# 1_Sch.net
KiCad netlist of a schematic drawn in Altium Designer
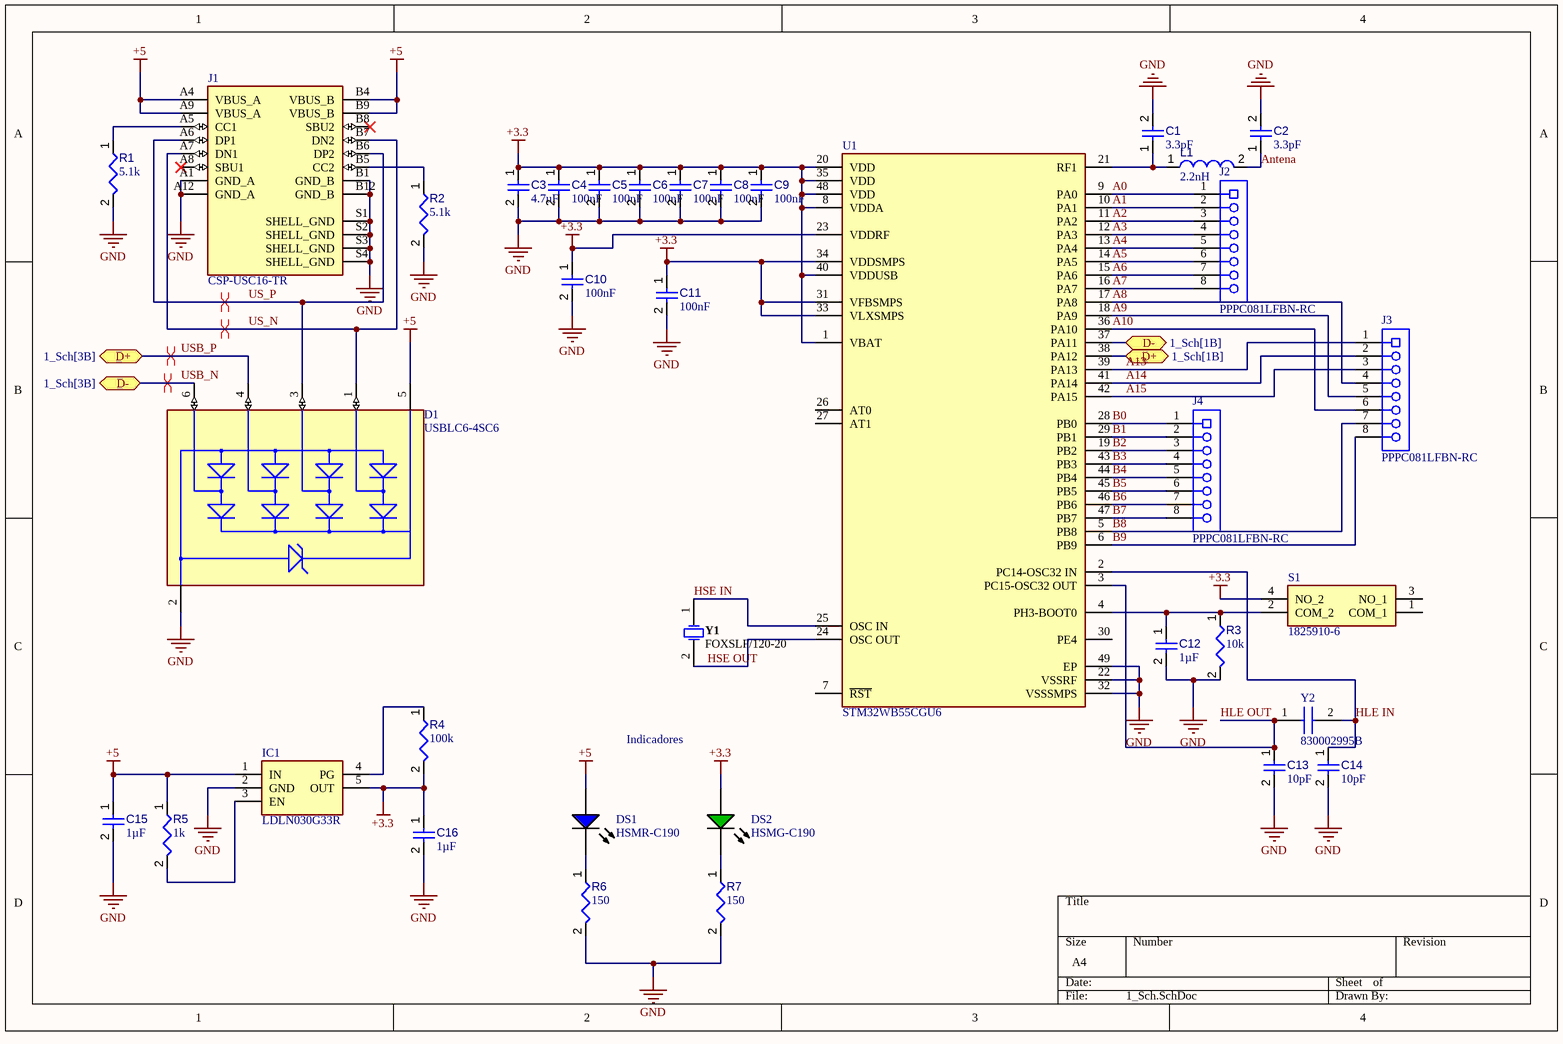
[diagram p0: 1_Sch.SchDoc]

(export (version "E")
  (design (tool "Eeschema 10.0.6"))
  (components
    (comp (ref "C1")
      (value "3.3pF")
      (footprint "CAPC1608X90X40NL10T20")
      (description "Chip Capacitor, 100 nF, +/- 10%, 50 V, 0603 (1608 Metric)")
      (fields (field (name "TOLERANCE") "10%") (field (name "Comment") "Capacitor 100 nF +/-10% 50 V 0603"))
      (libsource (lib "Universidad de Guadalajara") (part "CAP-NP-2"))
    )
    (comp (ref "C2")
      (value "3.3pF")
      (footprint "CAPC1608X90X40NL10T20")
      (description "Chip Capacitor, 100 nF, +/- 10%, 50 V, 0603 (1608 Metric)")
      (fields (field (name "TOLERANCE") "10%") (field (name "Comment") "Capacitor 100 nF +/-10% 50 V 0603"))
      (libsource (lib "Universidad de Guadalajara") (part "CAP-NP-2"))
    )
    (comp (ref "C3")
      (value "4.7uF")
      (footprint "CAPC1608X90X40NL10T20")
      (description "Chip Capacitor, 100 nF, +/- 10%, 50 V, 0603 (1608 Metric)")
      (fields (field (name "TOLERANCE") "10%") (field (name "Comment") "Capacitor 100 nF +/-10% 50 V 0603"))
      (libsource (lib "Universidad de Guadalajara") (part "CAP-NP-2"))
    )
    (comp (ref "C4")
      (value "100nF")
      (footprint "CAPC1608X90X40NL10T20")
      (description "Chip Capacitor, 100 nF, +/- 10%, 50 V, 0603 (1608 Metric)")
      (fields (field (name "TOLERANCE") "10%") (field (name "Comment") "Capacitor 100 nF +/-10% 50 V 0603"))
      (libsource (lib "Universidad de Guadalajara") (part "CAP-NP-2"))
    )
    (comp (ref "C5")
      (value "100nF")
      (footprint "CAPC1608X90X40NL10T20")
      (description "Chip Capacitor, 100 nF, +/- 10%, 50 V, 0603 (1608 Metric)")
      (fields (field (name "TOLERANCE") "10%") (field (name "Comment") "Capacitor 100 nF +/-10% 50 V 0603"))
      (libsource (lib "Universidad de Guadalajara") (part "CAP-NP-2"))
    )
    (comp (ref "C6")
      (value "100nF")
      (footprint "CAPC1608X90X40NL10T20")
      (description "Chip Capacitor, 100 nF, +/- 10%, 50 V, 0603 (1608 Metric)")
      (fields (field (name "TOLERANCE") "10%") (field (name "Comment") "Capacitor 100 nF +/-10% 50 V 0603"))
      (libsource (lib "Universidad de Guadalajara") (part "CAP-NP-2"))
    )
    (comp (ref "C7")
      (value "100nF")
      (footprint "CAPC1608X90X40NL10T20")
      (description "Chip Capacitor, 100 nF, +/- 10%, 50 V, 0603 (1608 Metric)")
      (fields (field (name "TOLERANCE") "10%") (field (name "Comment") "Capacitor 100 nF +/-10% 50 V 0603"))
      (libsource (lib "Universidad de Guadalajara") (part "CAP-NP-2"))
    )
    (comp (ref "C8")
      (value "100nF")
      (footprint "CAPC1608X90X40NL10T20")
      (description "Chip Capacitor, 100 nF, +/- 10%, 50 V, 0603 (1608 Metric)")
      (fields (field (name "TOLERANCE") "10%") (field (name "Comment") "Capacitor 100 nF +/-10% 50 V 0603"))
      (libsource (lib "Universidad de Guadalajara") (part "CAP-NP-2"))
    )
    (comp (ref "C9")
      (value "100nF")
      (footprint "CAPC1608X90X40NL10T20")
      (description "Chip Capacitor, 100 nF, +/- 10%, 50 V, 0603 (1608 Metric)")
      (fields (field (name "TOLERANCE") "10%") (field (name "Comment") "Capacitor 100 nF +/-10% 50 V 0603"))
      (libsource (lib "Universidad de Guadalajara") (part "CAP-NP-2"))
    )
    (comp (ref "C10")
      (value "100nF")
      (footprint "CAPC1608X90X40NL10T20")
      (description "Chip Capacitor, 100 nF, +/- 10%, 50 V, 0603 (1608 Metric)")
      (fields (field (name "TOLERANCE") "10%") (field (name "Comment") "Capacitor 100 nF +/-10% 50 V 0603"))
      (libsource (lib "Universidad de Guadalajara") (part "CAP-NP-2"))
    )
    (comp (ref "C11")
      (value "100nF")
      (footprint "CAPC1608X90X40NL10T20")
      (description "Chip Capacitor, 100 nF, +/- 10%, 50 V, 0603 (1608 Metric)")
      (fields (field (name "TOLERANCE") "10%") (field (name "Comment") "Capacitor 100 nF +/-10% 50 V 0603"))
      (libsource (lib "Universidad de Guadalajara") (part "CAP-NP-2"))
    )
    (comp (ref "C12")
      (value "1µF")
      (footprint "CAPC1608X94X35NL15T15")
      (description "Chip Capacitor, 1 uF, +/- 10%, 16 V, 0603 (1608 Metric)")
      (fields (field (name "TOLERANCE") "10%") (field (name "Comment") "Capacitor 1 uF +/- 10% 16 V 0603"))
      (libsource (lib "Universidad de Guadalajara") (part "CAP-NP-2"))
    )
    (comp (ref "C13")
      (value "10pF")
      (footprint "CAPC1608X90X40ML10T20")
      (description "Chip Capacitor, 10 pF, +/- 5%, 50 V, 0603 (1608 Metric)")
      (fields (field (name "TOLERANCE") "5%") (field (name "Comment") "Capacitor 10 pF +/- 5% 50 V 0603"))
      (libsource (lib "Universidad de Guadalajara") (part "CAP-NP-2"))
    )
    (comp (ref "C14")
      (value "10pF")
      (footprint "CAPC1608X90X40ML10T20")
      (description "Chip Capacitor, 10 pF, +/- 5%, 50 V, 0603 (1608 Metric)")
      (fields (field (name "TOLERANCE") "5%") (field (name "Comment") "Capacitor 10 pF +/- 5% 50 V 0603"))
      (libsource (lib "Universidad de Guadalajara") (part "CAP-NP-2"))
    )
    (comp (ref "C15")
      (value "1µF")
      (footprint "CAPC1608X90X35ML15T15")
      (description "Chip Capacitor, 1 uF, +/- 10%, 16 V, 0603 (1608 Metric)")
      (fields (field (name "TOLERANCE") "10%") (field (name "Comment") "Capacitor 1uF +/- 10% 16V 0603"))
      (libsource (lib "Universidad de Guadalajara") (part "CAP-NP-2"))
    )
    (comp (ref "C16")
      (value "1µF")
      (footprint "CAPC1608X90X35ML15T15")
      (description "Chip Capacitor, 1 uF, +/- 10%, 16 V, 0603 (1608 Metric)")
      (fields (field (name "TOLERANCE") "10%") (field (name "Comment") "Capacitor 1uF +/- 10% 16V 0603"))
      (libsource (lib "Universidad de Guadalajara") (part "CAP-NP-2"))
    )
    (comp (ref "D1")
      (value "USBLC6-4SC6")
      (footprint "FP-SOT23-6L-MFG")
      (description "TVS DIODE 5.25V 17V SOT23-6")
      (fields
        (field (name "MANUFACTURER") "STMicroelectronics")
        (field (name "OCTOPART") "https://octopart.com/usblc6-4sc6-stmicroelectronics-347147")
      )
      (libsource (lib "Altium Content Vault") (part "3e70b616ccdc4c88b528e1820c4a7da"))
    )
    (comp (ref "DS1")
      (value "HSMR-C190")
      (footprint "AVAG-HSMX-C190_V")
      (description "LED Uni-Color Blue, 78 mW, 20 mA, -40 to 85 degC, 2-Pin SMD, RoHS, Tape and Reel")
      (fields (field (name "POWER") "78mW") (field (name "MANUFACTURER") "Avago"))
      (libsource (lib "Universidad de Guadalajara") (part "LED-BLUE-AK-2"))
    )
    (comp (ref "DS2")
      (value "HSMG-C190")
      (footprint "AVAG-HSMX-C190_V")
      (description "LED Uni-Color Green, 52 mW, 20 mA, -40 to 85 degC, 2-Pin SMD, RoHS, Tape and Reel")
      (fields (field (name "POWER") "52mW") (field (name "MANUFACTURER") "Avago"))
      (libsource (lib "Universidad de Guadalajara") (part "LED-GREEN-AK-2"))
    )
    (comp (ref "IC1")
      (value "LDLN030G33R")
      (footprint "SamacSys:SOT95P280X100-5N")
      (description "Integrated Circuit")
      (fields (field (name "MOUSER PART NUMBER") "511-LDLN030G33R"))
      (libsource (lib "SamacSys") (part "LDLN030G33R"))
    )
    (comp (ref "J1")
      (value "CSP-USC16-TR")
      (footprint "VALCON_CSP-USC16-TR")
      (description "CSP-USC16-TR Valcon USB Type C Surface Mount PCB Socket")
      (fields (field (name "MF") "Valcon"))
      (libsource (lib "Universidad de Guadalajara") (part "CSP-USC16-TR"))
    )
    (comp (ref "J2")
      (value "PPPC081LFBN-RC")
      (footprint "SLIN-PPPC081LFBN-RC_V")
      (fields (field (name "MANUFACTURER") "Sullins"))
      (libsource (lib "Universidad de Guadalajara") (part "CN-1P-F-R8"))
    )
    (comp (ref "J3")
      (value "PPPC081LFBN-RC")
      (footprint "SLIN-PPPC081LFBN-RC_V")
      (fields (field (name "MANUFACTURER") "Sullins"))
      (libsource (lib "Universidad de Guadalajara") (part "CN-1P-F-R8"))
    )
    (comp (ref "J4")
      (value "PPPC081LFBN-RC")
      (footprint "SLIN-PPPC081LFBN-RC_V")
      (fields (field (name "MANUFACTURER") "Sullins"))
      (libsource (lib "Universidad de Guadalajara") (part "CN-1P-F-R8"))
    )
    (comp (ref "L1")
      (value "2.2nH")
      (footprint "IND1005X55X20VL5T10")
      (description "Chip Inductor, 2.2 nH, +/- 0.3 nH, 400 mA, -40 to 85 degC, 0402 (1005 Metric), RoHS, Tape and Reel")
      (fields (field (name "MANUFACTURER") "Panasonic") (field (name "TOLERANCE") "5%"))
      (libsource (lib "Universidad de Guadalajara") (part "IND-2"))
    )
    (comp (ref "R1")
      (value "5.1k")
      (footprint "RESC1608X55X25ML10T15")
      (description "Chip Resistor, 1 KOhm, +/-1%, 0.1 W, -55 to 155 degC, 0603 (1608 Metric)")
      (fields (field (name "POWER") "100mW") (field (name "TOLERANCE") "1%"))
      (libsource (lib "Universidad de Guadalajara") (part "RES-2"))
    )
    (comp (ref "R2")
      (value "5.1k")
      (footprint "RESC1608X55X25ML10T15")
      (description "Chip Resistor, 1 KOhm, +/-1%, 0.1 W, -55 to 155 degC, 0603 (1608 Metric)")
      (fields (field (name "POWER") "100mW") (field (name "TOLERANCE") "1%"))
      (libsource (lib "Universidad de Guadalajara") (part "RES-2"))
    )
    (comp (ref "R3")
      (value "10k")
      (footprint "RESC1608X55X25ML10T15")
      (description "Chip Resistor, 10 KOhm, +/- 1%, 01 W, -55 to 155 degC, 0603 (1608 Metric)")
      (fields (field (name "POWER") "100mW") (field (name "TOLERANCE") "1%"))
      (libsource (lib "Universidad de Guadalajara") (part "RES-2"))
    )
    (comp (ref "R4")
      (value "100k")
      (footprint "RESC1608X55X25ML10T15")
      (description "Chip Resistor, 100 KOhm, +/- 1%, 0.1 W, -55 to 155 degC, 0603 (1608 Metric)")
      (fields (field (name "TOLERANCE") "1%") (field (name "POWER") "100mW"))
      (libsource (lib "Universidad de Guadalajara") (part "RES-2"))
    )
    (comp (ref "R5")
      (value "1k")
      (footprint "RESC1608X55X25ML10T15")
      (description "Chip Resistor, 1 KOhm, +/-1%, 0.1 W, -55 to 155 degC, 0603 (1608 Metric)")
      (fields (field (name "POWER") "100mW") (field (name "TOLERANCE") "1%"))
      (libsource (lib "Universidad de Guadalajara") (part "RES-2"))
    )
    (comp (ref "R6")
      (value "150")
      (footprint "RESC1608X55X25ML10T15")
      (description "Chip Resistor, 1 KOhm, +/-1%, 0.1 W, -55 to 155 degC, 0603 (1608 Metric)")
      (fields (field (name "POWER") "100mW") (field (name "TOLERANCE") "1%"))
      (libsource (lib "Universidad de Guadalajara") (part "RES-2"))
    )
    (comp (ref "R7")
      (value "150")
      (footprint "RESC1608X55X25ML10T15")
      (description "Chip Resistor, 1 KOhm, +/-1%, 0.1 W, -55 to 155 degC, 0603 (1608 Metric)")
      (fields (field (name "POWER") "100mW") (field (name "TOLERANCE") "1%"))
      (libsource (lib "Universidad de Guadalajara") (part "RES-2"))
    )
    (comp (ref "S1")
      (value "1825910-6")
      (footprint "SamacSys:18259106")
      (description "Switch")
      (libsource (lib "*") (part "1825910-6"))
    )
    (comp (ref "U1")
      (value "STM32WB55CGU6")
      (footprint "FP-STM32WB55CGU6-MFG")
      (description "ULTRA-LOW-POWER DUAL CORE ARM CO")
      (fields
        (field (name "OCTOPART") "https://octopart.com/stm32wb55cgu6-stmicroelectronics-98750847")
        (field (name "MANUFACTURER") "STMicroelectronics")
      )
      (libsource (lib "Altium Content Vault") (part "9d9ca7f3567da95c474f3f549f05e68"))
    )
    (comp (ref "Y1")
      (value "FOXSLF/120-20")
      (footprint "FOX-FOXSLF-2_V")
      (description "Resistance Weld Thru-Hole Crystal, 12 MHz, +/-30 ppm, 20 pF, -20 to 70 degC, 2-Pin THD, RoHS, Bulk")
      (fields (field (name "MANUFACTURER") "FOX Electronics") (field (name "TOLERANCE") "50ppm"))
      (libsource (lib "Universidad de Guadalajara") (part "XTAL-1-2-2"))
    )
    (comp (ref "Y2")
      (value "830002995B")
      (footprint "SamacSys:830002995B")
      (description "Capacitor")
      (fields (field (name "MOUSER PART NUMBER") "710-830002995B"))
      (libsource (lib "*") (part "830002995B"))
    )
  )
  (nets
    (net (code "1") (name "+3.3") (class "Default")
      (node (ref "C10") (pin "1") (pinfunction "1_1") (pintype "passive"))
      (node (ref "C11") (pin "1") (pinfunction "1_1") (pintype "passive"))
      (node (ref "C16") (pin "1") (pinfunction "1_1") (pintype "passive"))
      (node (ref "C3") (pin "1") (pinfunction "1_1") (pintype "passive"))
      (node (ref "C4") (pin "1") (pinfunction "1_1") (pintype "passive"))
      (node (ref "C5") (pin "1") (pinfunction "1_1") (pintype "passive"))
      (node (ref "C6") (pin "1") (pinfunction "1_1") (pintype "passive"))
      (node (ref "C7") (pin "1") (pinfunction "1_1") (pintype "passive"))
      (node (ref "C8") (pin "1") (pinfunction "1_1") (pintype "passive"))
      (node (ref "C9") (pin "1") (pinfunction "1_1") (pintype "passive"))
      (node (ref "DS2") (pin "1") (pinfunction "A_1") (pintype "passive"))
      (node (ref "IC1") (pin "5") (pinfunction "OUT_5") (pintype "passive"))
      (node (ref "R4") (pin "2") (pinfunction "2_2") (pintype "passive"))
      (node (ref "S1") (pin "4") (pinfunction "NO_2_4") (pintype "passive"))
      (node (ref "U1") (pin "1") (pinfunction "VBAT_1") (pintype "passive"))
      (node (ref "U1") (pin "20") (pinfunction "VDD_20") (pintype "passive"))
      (node (ref "U1") (pin "23") (pinfunction "VDDRF_23") (pintype "passive"))
      (node (ref "U1") (pin "31") (pinfunction "VFBSMPS_31") (pintype "passive"))
      (node (ref "U1") (pin "33") (pinfunction "VLXSMPS_33") (pintype "passive"))
      (node (ref "U1") (pin "34") (pinfunction "VDDSMPS_34") (pintype "passive"))
      (node (ref "U1") (pin "35") (pinfunction "VDD_35") (pintype "passive"))
      (node (ref "U1") (pin "40") (pinfunction "VDDUSB_40") (pintype "passive"))
      (node (ref "U1") (pin "48") (pinfunction "VDD_48") (pintype "passive"))
      (node (ref "U1") (pin "8") (pinfunction "VDDA_8") (pintype "passive"))
    )
    (net (code "2") (name "+5") (class "Default")
      (node (ref "C15") (pin "1") (pinfunction "1_1") (pintype "passive"))
      (node (ref "D1") (pin "5") (pinfunction "VBUS_5") (pintype "power_in"))
      (node (ref "DS1") (pin "1") (pinfunction "A_1") (pintype "passive"))
      (node (ref "IC1") (pin "1") (pinfunction "IN_1") (pintype "passive"))
      (node (ref "J1") (pin "A4") (pinfunction "VBUS_A_A4") (pintype "power_in"))
      (node (ref "J1") (pin "A9") (pinfunction "VBUS_A_A9") (pintype "power_in"))
      (node (ref "J1") (pin "B4") (pinfunction "VBUS_B_B4") (pintype "power_in"))
      (node (ref "J1") (pin "B9") (pinfunction "VBUS_B_B9") (pintype "power_in"))
      (node (ref "R5") (pin "1") (pinfunction "1_1") (pintype "passive"))
    )
    (net (code "3") (name "/A0") (class "Default")
      (node (ref "J2") (pin "1") (pinfunction "1_1") (pintype "passive"))
      (node (ref "U1") (pin "9") (pinfunction "PA0_9") (pintype "passive"))
    )
    (net (code "4") (name "/A1") (class "Default")
      (node (ref "J2") (pin "2") (pinfunction "2_2") (pintype "passive"))
      (node (ref "U1") (pin "10") (pinfunction "PA1_10") (pintype "passive"))
    )
    (net (code "5") (name "/A2") (class "Default")
      (node (ref "J2") (pin "3") (pinfunction "3_3") (pintype "passive"))
      (node (ref "U1") (pin "11") (pinfunction "PA2_11") (pintype "passive"))
    )
    (net (code "6") (name "/A3") (class "Default")
      (node (ref "J2") (pin "4") (pinfunction "4_4") (pintype "passive"))
      (node (ref "U1") (pin "12") (pinfunction "PA3_12") (pintype "passive"))
    )
    (net (code "7") (name "/A4") (class "Default")
      (node (ref "J2") (pin "5") (pinfunction "5_5") (pintype "passive"))
      (node (ref "U1") (pin "13") (pinfunction "PA4_13") (pintype "passive"))
    )
    (net (code "8") (name "/A5") (class "Default")
      (node (ref "J2") (pin "6") (pinfunction "6_6") (pintype "passive"))
      (node (ref "U1") (pin "14") (pinfunction "PA5_14") (pintype "passive"))
    )
    (net (code "9") (name "/A6") (class "Default")
      (node (ref "J2") (pin "7") (pinfunction "7_7") (pintype "passive"))
      (node (ref "U1") (pin "15") (pinfunction "PA6_15") (pintype "passive"))
    )
    (net (code "10") (name "/A7") (class "Default")
      (node (ref "J2") (pin "8") (pinfunction "8_8") (pintype "passive"))
      (node (ref "U1") (pin "16") (pinfunction "PA7_16") (pintype "passive"))
    )
    (net (code "11") (name "/A8") (class "Default")
      (node (ref "J3") (pin "4") (pinfunction "4_4") (pintype "passive"))
      (node (ref "U1") (pin "17") (pinfunction "PA8_17") (pintype "passive"))
    )
    (net (code "12") (name "/A9") (class "Default")
      (node (ref "J3") (pin "5") (pinfunction "5_5") (pintype "passive"))
      (node (ref "U1") (pin "18") (pinfunction "PA9_18") (pintype "passive"))
    )
    (net (code "13") (name "/A10") (class "Default")
      (node (ref "J3") (pin "6") (pinfunction "6_6") (pintype "passive"))
      (node (ref "U1") (pin "36") (pinfunction "PA10_36") (pintype "passive"))
    )
    (net (code "14") (name "/A13") (class "Default")
      (node (ref "J3") (pin "1") (pinfunction "1_1") (pintype "passive"))
      (node (ref "U1") (pin "39") (pinfunction "PA13_39") (pintype "passive"))
    )
    (net (code "15") (name "/A14") (class "Default")
      (node (ref "J3") (pin "2") (pinfunction "2_2") (pintype "passive"))
      (node (ref "U1") (pin "41") (pinfunction "PA14_41") (pintype "passive"))
    )
    (net (code "16") (name "/A15") (class "Default")
      (node (ref "J3") (pin "3") (pinfunction "3_3") (pintype "passive"))
      (node (ref "U1") (pin "42") (pinfunction "PA15_42") (pintype "passive"))
    )
    (net (code "17") (name "/Antena") (class "Default")
      (node (ref "C2") (pin "1") (pinfunction "1_1") (pintype "passive"))
      (node (ref "L1") (pin "2") (pinfunction "2_2") (pintype "passive"))
    )
    (net (code "18") (name "/B0") (class "Default")
      (node (ref "J4") (pin "1") (pinfunction "1_1") (pintype "passive"))
      (node (ref "U1") (pin "28") (pinfunction "PB0_28") (pintype "passive"))
    )
    (net (code "19") (name "/B1") (class "Default")
      (node (ref "J4") (pin "2") (pinfunction "2_2") (pintype "passive"))
      (node (ref "U1") (pin "29") (pinfunction "PB1_29") (pintype "passive"))
    )
    (net (code "20") (name "/B2") (class "Default")
      (node (ref "J4") (pin "3") (pinfunction "3_3") (pintype "passive"))
      (node (ref "U1") (pin "19") (pinfunction "PB2_19") (pintype "passive"))
    )
    (net (code "21") (name "/B3") (class "Default")
      (node (ref "J4") (pin "4") (pinfunction "4_4") (pintype "passive"))
      (node (ref "U1") (pin "43") (pinfunction "PB3_43") (pintype "passive"))
    )
    (net (code "22") (name "/B4") (class "Default")
      (node (ref "J4") (pin "5") (pinfunction "5_5") (pintype "passive"))
      (node (ref "U1") (pin "44") (pinfunction "PB4_44") (pintype "passive"))
    )
    (net (code "23") (name "/B5") (class "Default")
      (node (ref "J4") (pin "6") (pinfunction "6_6") (pintype "passive"))
      (node (ref "U1") (pin "45") (pinfunction "PB5_45") (pintype "passive"))
    )
    (net (code "24") (name "/B6") (class "Default")
      (node (ref "J4") (pin "7") (pinfunction "7_7") (pintype "passive"))
      (node (ref "U1") (pin "46") (pinfunction "PB6_46") (pintype "passive"))
    )
    (net (code "25") (name "/B7") (class "Default")
      (node (ref "J4") (pin "8") (pinfunction "8_8") (pintype "passive"))
      (node (ref "U1") (pin "47") (pinfunction "PB7_47") (pintype "passive"))
    )
    (net (code "26") (name "/B8") (class "Default")
      (node (ref "J3") (pin "7") (pinfunction "7_7") (pintype "passive"))
      (node (ref "U1") (pin "5") (pinfunction "PB8_5") (pintype "passive"))
    )
    (net (code "27") (name "/B9") (class "Default")
      (node (ref "J3") (pin "8") (pinfunction "8_8") (pintype "passive"))
      (node (ref "U1") (pin "6") (pinfunction "PB9_6") (pintype "passive"))
    )
    (net (code "28") (name "/HLE IN") (class "Default")
      (node (ref "C14") (pin "1") (pinfunction "1_1") (pintype "passive"))
      (node (ref "U1") (pin "2") (pinfunction "PC14-OSC32_IN_2") (pintype "passive"))
      (node (ref "Y2") (pin "2") (pinfunction "CRYSTAL_2_2") (pintype "passive"))
    )
    (net (code "29") (name "/HLE OUT") (class "Default")
      (node (ref "C13") (pin "1") (pinfunction "1_1") (pintype "passive"))
      (node (ref "U1") (pin "3") (pinfunction "PC15-OSC32_OUT_3") (pintype "passive"))
      (node (ref "Y2") (pin "1") (pinfunction "CRYSTAL_1_1") (pintype "passive"))
    )
    (net (code "30") (name "/HSE IN") (class "Default")
      (node (ref "U1") (pin "25") (pinfunction "OSC_IN_25") (pintype "passive"))
      (node (ref "Y1") (pin "1") (pinfunction "1_1") (pintype "passive"))
    )
    (net (code "31") (name "/HSE OUT") (class "Default")
      (node (ref "U1") (pin "24") (pinfunction "OSC_OUT_24") (pintype "passive"))
      (node (ref "Y1") (pin "2") (pinfunction "2_2") (pintype "passive"))
    )
    (net (code "32") (name "/USB_N") (class "Default")
      (node (ref "D1") (pin "6") (pinfunction "I/O4_6") (pintype "bidirectional"))
      (node (ref "U1") (pin "37") (pinfunction "PA11_37") (pintype "passive"))
    )
    (net (code "33") (name "/USB_P") (class "Default")
      (node (ref "D1") (pin "4") (pinfunction "I/O3_4") (pintype "bidirectional"))
      (node (ref "U1") (pin "38") (pinfunction "PA12_38") (pintype "passive"))
    )
    (net (code "34") (name "/US_N") (class "Default")
      (node (ref "D1") (pin "1") (pinfunction "I/O1_1") (pintype "bidirectional"))
      (node (ref "J1") (pin "A7") (pinfunction "DN1_A7") (pintype "bidirectional"))
      (node (ref "J1") (pin "B7") (pinfunction "DN2_B7") (pintype "bidirectional"))
    )
    (net (code "35") (name "/US_P") (class "Default")
      (node (ref "D1") (pin "3") (pinfunction "I/O2_3") (pintype "bidirectional"))
      (node (ref "J1") (pin "A6") (pinfunction "DP1_A6") (pintype "bidirectional"))
      (node (ref "J1") (pin "B6") (pinfunction "DP2_B6") (pintype "bidirectional"))
    )
    (net (code "36") (name "GND") (class "Default")
      (node (ref "C1") (pin "2") (pinfunction "2_2") (pintype "passive"))
      (node (ref "C10") (pin "2") (pinfunction "2_2") (pintype "passive"))
      (node (ref "C11") (pin "2") (pinfunction "2_2") (pintype "passive"))
      (node (ref "C12") (pin "2") (pinfunction "2_2") (pintype "passive"))
      (node (ref "C13") (pin "2") (pinfunction "2_2") (pintype "passive"))
      (node (ref "C14") (pin "2") (pinfunction "2_2") (pintype "passive"))
      (node (ref "C15") (pin "2") (pinfunction "2_2") (pintype "passive"))
      (node (ref "C16") (pin "2") (pinfunction "2_2") (pintype "passive"))
      (node (ref "C2") (pin "2") (pinfunction "2_2") (pintype "passive"))
      (node (ref "C3") (pin "2") (pinfunction "2_2") (pintype "passive"))
      (node (ref "C4") (pin "2") (pinfunction "2_2") (pintype "passive"))
      (node (ref "C5") (pin "2") (pinfunction "2_2") (pintype "passive"))
      (node (ref "C6") (pin "2") (pinfunction "2_2") (pintype "passive"))
      (node (ref "C7") (pin "2") (pinfunction "2_2") (pintype "passive"))
      (node (ref "C8") (pin "2") (pinfunction "2_2") (pintype "passive"))
      (node (ref "C9") (pin "2") (pinfunction "2_2") (pintype "passive"))
      (node (ref "D1") (pin "2") (pinfunction "GND_2") (pintype "power_in"))
      (node (ref "IC1") (pin "2") (pinfunction "GND_2") (pintype "passive"))
      (node (ref "J1") (pin "A1") (pinfunction "GND_A_A1") (pintype "power_in"))
      (node (ref "J1") (pin "A12") (pinfunction "GND_A_A12") (pintype "power_in"))
      (node (ref "J1") (pin "B1") (pinfunction "GND_B_B1") (pintype "power_in"))
      (node (ref "J1") (pin "B12") (pinfunction "GND_B_B12") (pintype "power_in"))
      (node (ref "J1") (pin "S1") (pinfunction "SHELL_GND_S1") (pintype "power_in"))
      (node (ref "J1") (pin "S2") (pinfunction "SHELL_GND_S2") (pintype "power_in"))
      (node (ref "J1") (pin "S3") (pinfunction "SHELL_GND_S3") (pintype "power_in"))
      (node (ref "J1") (pin "S4") (pinfunction "SHELL_GND_S4") (pintype "power_in"))
      (node (ref "R1") (pin "2") (pinfunction "2_2") (pintype "passive"))
      (node (ref "R2") (pin "2") (pinfunction "2_2") (pintype "passive"))
      (node (ref "R3") (pin "2") (pinfunction "2_2") (pintype "passive"))
      (node (ref "R6") (pin "2") (pinfunction "2_2") (pintype "passive"))
      (node (ref "R7") (pin "2") (pinfunction "2_2") (pintype "passive"))
      (node (ref "U1") (pin "22") (pinfunction "VSSRF_22") (pintype "passive"))
      (node (ref "U1") (pin "32") (pinfunction "VSSSMPS_32") (pintype "passive"))
      (node (ref "U1") (pin "49") (pinfunction "EP_49") (pintype "power_in"))
    )
    (net (code "37") (name "Net-(DS1-K)") (class "Default")
      (node (ref "DS1") (pin "2") (pinfunction "K_2") (pintype "passive"))
      (node (ref "R6") (pin "1") (pinfunction "1_1") (pintype "passive"))
    )
    (net (code "38") (name "Net-(DS2-K)") (class "Default")
      (node (ref "DS2") (pin "2") (pinfunction "K_2") (pintype "passive"))
      (node (ref "R7") (pin "1") (pinfunction "1_1") (pintype "passive"))
    )
    (net (code "39") (name "Net-(IC1-EN)") (class "Default")
      (node (ref "IC1") (pin "3") (pinfunction "EN_3") (pintype "passive"))
      (node (ref "R5") (pin "2") (pinfunction "2_2") (pintype "passive"))
    )
    (net (code "40") (name "Net-(IC1-PG)") (class "Default")
      (node (ref "IC1") (pin "4") (pinfunction "PG_4") (pintype "passive"))
      (node (ref "R4") (pin "1") (pinfunction "1_1") (pintype "passive"))
    )
    (net (code "41") (name "Net-(J1-CC1)") (class "Default")
      (node (ref "J1") (pin "A5") (pinfunction "CC1_A5") (pintype "bidirectional"))
      (node (ref "R1") (pin "1") (pinfunction "1_1") (pintype "passive"))
    )
    (net (code "42") (name "Net-(J1-CC2)") (class "Default")
      (node (ref "J1") (pin "B5") (pinfunction "CC2_B5") (pintype "bidirectional"))
      (node (ref "R2") (pin "1") (pinfunction "1_1") (pintype "passive"))
    )
    (net (code "43") (name "Net-(S1-COM_2)") (class "Default")
      (node (ref "C12") (pin "1") (pinfunction "1_1") (pintype "passive"))
      (node (ref "R3") (pin "1") (pinfunction "1_1") (pintype "passive"))
      (node (ref "S1") (pin "2") (pinfunction "COM_2_2") (pintype "passive"))
      (node (ref "U1") (pin "4") (pinfunction "PH3-BOOT0_4") (pintype "passive"))
    )
    (net (code "44") (name "Net-(U1-RF1)") (class "Default")
      (node (ref "C1") (pin "1") (pinfunction "1_1") (pintype "passive"))
      (node (ref "L1") (pin "1") (pinfunction "1_1") (pintype "passive"))
      (node (ref "U1") (pin "21") (pinfunction "RF1_21") (pintype "passive"))
    )
    (net (code "45") (name "unconnected-(J1-SBU1-PadA8)") (class "Default")
      (node (ref "J1") (pin "A8") (pinfunction "SBU1_A8") (pintype "bidirectional+no_connect"))
    )
    (net (code "46") (name "unconnected-(J1-SBU2-PadB8)") (class "Default")
      (node (ref "J1") (pin "B8") (pinfunction "SBU2_B8") (pintype "bidirectional+no_connect"))
    )
    (net (code "47") (name "unconnected-(S1-COM_1-Pad1)") (class "Default")
      (node (ref "S1") (pin "1") (pinfunction "COM_1_1") (pintype "passive"))
    )
    (net (code "48") (name "unconnected-(S1-NO_1-Pad3)") (class "Default")
      (node (ref "S1") (pin "3") (pinfunction "NO_1_3") (pintype "passive"))
    )
    (net (code "49") (name "unconnected-(U1-AT0-Pad26)") (class "Default")
      (node (ref "U1") (pin "26") (pinfunction "AT0_26") (pintype "passive"))
    )
    (net (code "50") (name "unconnected-(U1-AT1-Pad27)") (class "Default")
      (node (ref "U1") (pin "27") (pinfunction "AT1_27") (pintype "passive"))
    )
    (net (code "51") (name "unconnected-(U1-PE4-Pad30)") (class "Default")
      (node (ref "U1") (pin "30") (pinfunction "PE4_30") (pintype "passive"))
    )
    (net (code "52") (name "unconnected-(U1-~{RST}-Pad7)") (class "Default")
      (node (ref "U1") (pin "7") (pinfunction "~{RST}_7") (pintype "passive"))
    )
  )
)
